# ClarityMezzanine_V2.net
KiCad netlist of a schematic drawn in Altium Designer
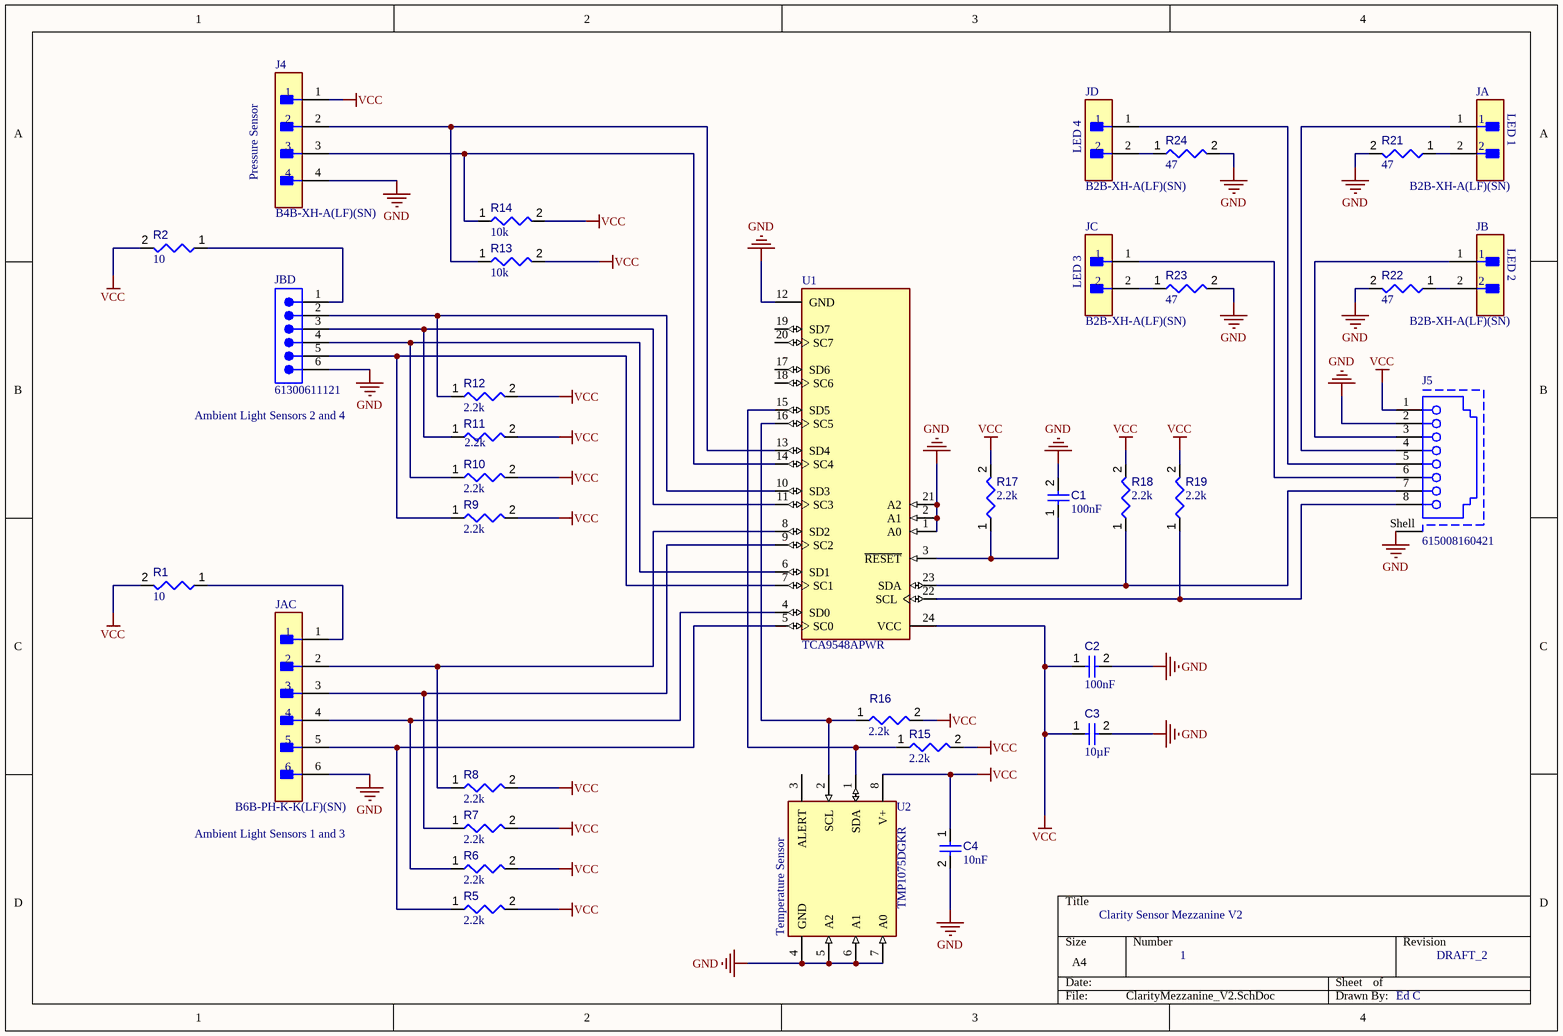
[diagram p0: ClarityMezzanine_V2.SchDoc]

(export (version "E")
  (design (tool "Eeschema 10.0.6"))
  (components
    (comp (ref "C1")
      (value "100nF")
      (footprint "CAPC2013X95X50LL10T25")
      (description "Chip Capacitor, 100 nF, +/- 10%, 50 V, 0805 (2012 Metric)")
      (fields (field (name "TOLERANCE") "10%") (field (name "Comment") "Capacitor 100 nF +/-10% 50 V 0805"))
      (libsource (lib "University of Auckland") (part "CAP-NP-2"))
    )
    (comp (ref "C2")
      (value "100nF")
      (footprint "CAPC2013X95X50LL10T25")
      (description "Chip Capacitor, 100 nF, +/- 10%, 50 V, 0805 (2012 Metric)")
      (fields (field (name "TOLERANCE") "10%") (field (name "Comment") "Capacitor 100 nF +/-10% 50 V 0805"))
      (libsource (lib "University of Auckland") (part "CAP-NP-2"))
    )
    (comp (ref "C3")
      (value "10µF")
      (footprint "CAPC0805(2012)145_L")
      (description "Chip Capacitor, 10µF +/-20%, 25V, 0805, Thickness 1.45 mm")
      (fields (field (name "TOLERANCE") "10%") (field (name "Comment") "Capacitor 10µF +/-20% 25V 0805"))
      (libsource (lib "University of Auckland") (part "CAP-NP-2"))
    )
    (comp (ref "C4")
      (value "10nF")
      (footprint "FP-C0805C-DN-IPC_A")
      (fields (field (name "Comment") "C0805C103K2RACTU"))
      (libsource (lib "University of Auckland") (part "CAP-NP-2"))
    )
    (comp (ref "J4")
      (value "B4B-XH-A(LF)(SN)")
      (footprint "FP-B4B-XH-A_LF_SN-MFG")
      (description "Header for PCB; pitch 2.50mm; 4-contacts; THT male; top entry; 250V/3A")
      (libsource (lib "University of Auckland") (part "299a8cea1bdcbc3624fe62c390fa72c"))
    )
    (comp (ref "J5")
      (value "615008160421")
      (footprint "615008160421")
      (description "Rj45 Connector, Jack, 8P8C, 1Port Rohs Compliant: Yes")
      (libsource (lib "University of Auckland") (part "8P8C - 1 Port - Shielded"))
    )
    (comp (ref "JA")
      (value "B2B-XH-A(LF)(SN)")
      (footprint "FP-B2B-XH-A_LF_SN-MFG")
      (description "CONNECTOR HEADER, XH SERIES, 2 POSITION, 2.50MM, Press-Fit Solder, Detent Lock, Natural")
      (libsource (lib "") (part "3bc925449376181038e59eaffc5286c_1"))
    )
    (comp (ref "JAC")
      (value "B6B-PH-K-K(LF)(SN)")
      (footprint "FP-B6B-PH-K-K_LF_SN-MFG")
      (description "PH Series 6 Position 2 mm Pitch Through Hole Top Entry Shrouded Header")
      (libsource (lib "University of Auckland") (part "f2cb566baf1c37ab5a3b8e90bbeafd6"))
    )
    (comp (ref "JB")
      (value "B2B-XH-A(LF)(SN)")
      (footprint "FP-B2B-XH-A_LF_SN-MFG")
      (description "CONNECTOR HEADER, XH SERIES, 2 POSITION, 2.50MM, Press-Fit Solder, Detent Lock, Natural")
      (libsource (lib "") (part "3bc925449376181038e59eaffc5286c_1"))
    )
    (comp (ref "JBD")
      (value "61300611121")
      (footprint "61300611121")
      (libsource (lib "University of Auckland") (part "Header_Male_1R_06P"))
    )
    (comp (ref "JC")
      (value "B2B-XH-A(LF)(SN)")
      (footprint "FP-B2B-XH-A_LF_SN-MFG")
      (description "CONNECTOR HEADER, XH SERIES, 2 POSITION, 2.50MM, Press-Fit Solder, Detent Lock, Natural")
      (libsource (lib "University of Auckland") (part "3bc925449376181038e59eaffc5286c"))
    )
    (comp (ref "JD")
      (value "B2B-XH-A(LF)(SN)")
      (footprint "FP-B2B-XH-A_LF_SN-MFG")
      (description "CONNECTOR HEADER, XH SERIES, 2 POSITION, 2.50MM, Press-Fit Solder, Detent Lock, Natural")
      (libsource (lib "University of Auckland") (part "3bc925449376181038e59eaffc5286c"))
    )
    (comp (ref "R1")
      (value "10")
      (footprint "RESC2013X60X35ML10T20")
      (fields
        (field (name "TOLERANCE") "1%")
        (field (name "POWER") "125mW")
        (field (name "Comment") "RC0805FR-0710RL")
      )
      (libsource (lib "University of Auckland") (part "RES-2"))
    )
    (comp (ref "R2")
      (value "10")
      (footprint "RESC2013X60X35ML10T20")
      (fields
        (field (name "TOLERANCE") "1%")
        (field (name "POWER") "125mW")
        (field (name "Comment") "RC0805FR-0710RL")
      )
      (libsource (lib "University of Auckland") (part "RES-2"))
    )
    (comp (ref "R5")
      (value "2.2k")
      (footprint "FP-CRCW0805-e3-IPC_A")
      (fields
        (field (name "POWER") "125mW")
        (field (name "TOLERANCE") "1%")
        (field (name "Comment") "CRCW08052K20FKEA")
      )
      (libsource (lib "University of Auckland") (part "RES-2"))
    )
    (comp (ref "R6")
      (value "2.2k")
      (footprint "FP-CRCW0805-e3-IPC_A")
      (fields
        (field (name "POWER") "125mW")
        (field (name "TOLERANCE") "1%")
        (field (name "Comment") "CRCW08052K20FKEA")
      )
      (libsource (lib "University of Auckland") (part "RES-2"))
    )
    (comp (ref "R7")
      (value "2.2k")
      (footprint "FP-CRCW0805-e3-IPC_A")
      (fields
        (field (name "POWER") "125mW")
        (field (name "TOLERANCE") "1%")
        (field (name "Comment") "CRCW08052K20FKEA")
      )
      (libsource (lib "University of Auckland") (part "RES-2"))
    )
    (comp (ref "R8")
      (value "2.2k")
      (footprint "FP-CRCW0805-e3-IPC_A")
      (fields
        (field (name "POWER") "125mW")
        (field (name "TOLERANCE") "1%")
        (field (name "Comment") "CRCW08052K20FKEA")
      )
      (libsource (lib "University of Auckland") (part "RES-2"))
    )
    (comp (ref "R9")
      (value "2.2k")
      (footprint "FP-CRCW0805-e3-IPC_A")
      (fields
        (field (name "POWER") "125mW")
        (field (name "TOLERANCE") "1%")
        (field (name "Comment") "CRCW08052K20FKEA")
      )
      (libsource (lib "University of Auckland") (part "RES-2"))
    )
    (comp (ref "R10")
      (value "2.2k")
      (footprint "FP-CRCW0805-e3-IPC_A")
      (fields
        (field (name "POWER") "125mW")
        (field (name "TOLERANCE") "1%")
        (field (name "Comment") "CRCW08052K20FKEA")
      )
      (libsource (lib "University of Auckland") (part "RES-2"))
    )
    (comp (ref "R11")
      (value "2.2k")
      (footprint "FP-CRCW0805-e3-IPC_A")
      (fields
        (field (name "POWER") "125mW")
        (field (name "TOLERANCE") "1%")
        (field (name "Comment") "CRCW08052K20FKEA")
      )
      (libsource (lib "University of Auckland") (part "RES-2"))
    )
    (comp (ref "R12")
      (value "2.2k")
      (footprint "FP-CRCW0805-e3-IPC_A")
      (fields
        (field (name "POWER") "125mW")
        (field (name "TOLERANCE") "1%")
        (field (name "Comment") "CRCW08052K20FKEA")
      )
      (libsource (lib "University of Auckland") (part "RES-2"))
    )
    (comp (ref "R13")
      (value "10k")
      (footprint "RESC2013X50X35ML15T15")
      (description "Chip Resistor, 10 KOhm, +/- 1%, 125 mW, -55 to 155 degC, 0805 (2012 Metric)")
      (fields (field (name "TOLERANCE") "1%") (field (name "POWER") "125mW"))
      (libsource (lib "University of Auckland") (part "RES-2"))
    )
    (comp (ref "R14")
      (value "10k")
      (footprint "RESC2013X50X35ML15T15")
      (description "Chip Resistor, 10 KOhm, +/- 1%, 125 mW, -55 to 155 degC, 0805 (2012 Metric)")
      (fields (field (name "TOLERANCE") "1%") (field (name "POWER") "125mW"))
      (libsource (lib "University of Auckland") (part "RES-2"))
    )
    (comp (ref "R15")
      (value "2.2k")
      (footprint "FP-CRCW0805-e3-IPC_A")
      (fields
        (field (name "POWER") "125mW")
        (field (name "TOLERANCE") "1%")
        (field (name "Comment") "CRCW08052K20FKEA")
      )
      (libsource (lib "University of Auckland") (part "RES-2"))
    )
    (comp (ref "R16")
      (value "2.2k")
      (footprint "FP-CRCW0805-e3-IPC_A")
      (fields
        (field (name "POWER") "125mW")
        (field (name "TOLERANCE") "1%")
        (field (name "Comment") "CRCW08052K20FKEA")
      )
      (libsource (lib "University of Auckland") (part "RES-2"))
    )
    (comp (ref "R17")
      (value "2.2k")
      (footprint "FP-CRCW0805-e3-IPC_A")
      (fields
        (field (name "POWER") "125mW")
        (field (name "TOLERANCE") "1%")
        (field (name "Comment") "CRCW08052K20FKEA")
      )
      (libsource (lib "University of Auckland") (part "RES-2"))
    )
    (comp (ref "R18")
      (value "2.2k")
      (footprint "FP-CRCW0805-e3-IPC_A")
      (fields
        (field (name "POWER") "125mW")
        (field (name "TOLERANCE") "1%")
        (field (name "Comment") "CRCW08052K20FKEA")
      )
      (libsource (lib "University of Auckland") (part "RES-2"))
    )
    (comp (ref "R19")
      (value "2.2k")
      (footprint "FP-CRCW0805-e3-IPC_A")
      (fields
        (field (name "POWER") "125mW")
        (field (name "TOLERANCE") "1%")
        (field (name "Comment") "CRCW08052K20FKEA")
      )
      (libsource (lib "University of Auckland") (part "RES-2"))
    )
    (comp (ref "R21")
      (value "47")
      (footprint "FP-ERJ6EN-IPC_B")
      (fields
        (field (name "TOLERANCE") "1%")
        (field (name "POWER") "125mW")
        (field (name "Comment") "ERJ-6ENF47R0V")
      )
      (libsource (lib "University of Auckland") (part "RES-2"))
    )
    (comp (ref "R22")
      (value "47")
      (footprint "FP-ERJ6EN-IPC_B")
      (fields
        (field (name "TOLERANCE") "1%")
        (field (name "POWER") "125mW")
        (field (name "Comment") "ERJ-6ENF47R0V")
      )
      (libsource (lib "University of Auckland") (part "RES-2"))
    )
    (comp (ref "R23")
      (value "47")
      (footprint "FP-ERJ6EN-IPC_B")
      (fields
        (field (name "TOLERANCE") "1%")
        (field (name "POWER") "125mW")
        (field (name "Comment") "ERJ-6ENF47R0V")
      )
      (libsource (lib "University of Auckland") (part "RES-2"))
    )
    (comp (ref "R24")
      (value "47")
      (footprint "FP-ERJ6EN-IPC_B")
      (fields
        (field (name "TOLERANCE") "1%")
        (field (name "POWER") "125mW")
        (field (name "Comment") "ERJ-6ENF47R0V")
      )
      (libsource (lib "University of Auckland") (part "RES-2"))
    )
    (comp (ref "U1")
      (value "TCA9548APWR")
      (footprint "FP-PW0024A-MFG")
      (description "Multiplexer, 9548 Series, 1-Func, 1 Line Input, 8 Line Output, True Output, PDSO24")
      (libsource (lib "University of Auckland") (part "aab65143522579f0e88a32f493a4230"))
    )
    (comp (ref "U2")
      (value "TMP1075DGKR")
      (footprint "FP-DGK0008A-IPC_A")
      (description "Serial Switch/Digital Sensor, 12 Bit(s), 2Cel, Square, Surface Mount")
      (libsource (lib "University of Auckland") (part "bfddf12e45925052cd02cc7c071e68b"))
    )
  )
  (nets
    (net (code "1") (name "GND") (class "Default")
      (node (ref "C1") (pin "2") (pinfunction "2_2") (pintype "passive"))
      (node (ref "C2") (pin "2") (pinfunction "2_2") (pintype "passive"))
      (node (ref "C3") (pin "2") (pinfunction "2_2") (pintype "passive"))
      (node (ref "C4") (pin "2") (pinfunction "2_2") (pintype "passive"))
      (node (ref "J4") (pin "4") (pinfunction "4_4") (pintype "passive"))
      (node (ref "J5") (pin "2") (pinfunction "2_2") (pintype "passive"))
      (node (ref "J5") (pin "Shell") (pinfunction "Shell_Shell") (pintype "passive"))
      (node (ref "JAC") (pin "6") (pinfunction "6_6") (pintype "passive"))
      (node (ref "JBD") (pin "6") (pinfunction "6_6") (pintype "passive"))
      (node (ref "R21") (pin "2") (pinfunction "2_2") (pintype "passive"))
      (node (ref "R22") (pin "2") (pinfunction "2_2") (pintype "passive"))
      (node (ref "R23") (pin "2") (pinfunction "2_2") (pintype "passive"))
      (node (ref "R24") (pin "2") (pinfunction "2_2") (pintype "passive"))
      (node (ref "U1") (pin "1") (pinfunction "A0_1") (pintype "input"))
      (node (ref "U1") (pin "12") (pinfunction "GND_12") (pintype "power_in"))
      (node (ref "U1") (pin "2") (pinfunction "A1_2") (pintype "input"))
      (node (ref "U1") (pin "21") (pinfunction "A2_21") (pintype "input"))
      (node (ref "U2") (pin "4") (pinfunction "GND_4") (pintype "power_in"))
      (node (ref "U2") (pin "5") (pinfunction "A2_5") (pintype "input"))
      (node (ref "U2") (pin "6") (pinfunction "A1_6") (pintype "input"))
      (node (ref "U2") (pin "7") (pinfunction "A0_7") (pintype "input"))
    )
    (net (code "2") (name "Net-(J5-Pad3)") (class "Default")
      (node (ref "J5") (pin "3") (pinfunction "3_3") (pintype "passive"))
      (node (ref "JB") (pin "1") (pinfunction "1_1") (pintype "passive"))
    )
    (net (code "3") (name "Net-(J5-Pad4)") (class "Default")
      (node (ref "J5") (pin "4") (pinfunction "4_4") (pintype "passive"))
      (node (ref "JA") (pin "1") (pinfunction "1_1") (pintype "passive"))
    )
    (net (code "4") (name "Net-(J5-Pad5)") (class "Default")
      (node (ref "J5") (pin "5") (pinfunction "5_5") (pintype "passive"))
      (node (ref "JD") (pin "1") (pinfunction "1_1") (pintype "passive"))
    )
    (net (code "5") (name "Net-(J5-Pad6)") (class "Default")
      (node (ref "J5") (pin "6") (pinfunction "6_6") (pintype "passive"))
      (node (ref "JC") (pin "1") (pinfunction "1_1") (pintype "passive"))
    )
    (net (code "6") (name "Net-(JA-Pad2)") (class "Default")
      (node (ref "JA") (pin "2") (pinfunction "2_2") (pintype "passive"))
      (node (ref "R21") (pin "1") (pinfunction "1_1") (pintype "passive"))
    )
    (net (code "7") (name "Net-(JAC-Pad1)") (class "Default")
      (node (ref "JAC") (pin "1") (pinfunction "1_1") (pintype "passive"))
      (node (ref "R1") (pin "1") (pinfunction "1_1") (pintype "passive"))
    )
    (net (code "8") (name "Net-(JB-Pad2)") (class "Default")
      (node (ref "JB") (pin "2") (pinfunction "2_2") (pintype "passive"))
      (node (ref "R22") (pin "1") (pinfunction "1_1") (pintype "passive"))
    )
    (net (code "9") (name "Net-(JBD-Pad1)") (class "Default")
      (node (ref "JBD") (pin "1") (pinfunction "1_1") (pintype "passive"))
      (node (ref "R2") (pin "1") (pinfunction "1_1") (pintype "passive"))
    )
    (net (code "10") (name "Net-(JC-Pad2)") (class "Default")
      (node (ref "JC") (pin "2") (pinfunction "2_2") (pintype "passive"))
      (node (ref "R23") (pin "1") (pinfunction "1_1") (pintype "passive"))
    )
    (net (code "11") (name "Net-(JD-Pad2)") (class "Default")
      (node (ref "JD") (pin "2") (pinfunction "2_2") (pintype "passive"))
      (node (ref "R24") (pin "1") (pinfunction "1_1") (pintype "passive"))
    )
    (net (code "12") (name "Net-(U1-SC0)") (class "Default")
      (node (ref "JAC") (pin "5") (pinfunction "5_5") (pintype "passive"))
      (node (ref "R5") (pin "1") (pinfunction "1_1") (pintype "passive"))
      (node (ref "U1") (pin "5") (pinfunction "SC0_5") (pintype "bidirectional"))
    )
    (net (code "13") (name "Net-(U1-SC1)") (class "Default")
      (node (ref "JBD") (pin "5") (pinfunction "5_5") (pintype "passive"))
      (node (ref "R9") (pin "1") (pinfunction "1_1") (pintype "passive"))
      (node (ref "U1") (pin "7") (pinfunction "SC1_7") (pintype "bidirectional"))
    )
    (net (code "14") (name "Net-(U1-SC2)") (class "Default")
      (node (ref "JAC") (pin "3") (pinfunction "3_3") (pintype "passive"))
      (node (ref "R7") (pin "1") (pinfunction "1_1") (pintype "passive"))
      (node (ref "U1") (pin "9") (pinfunction "SC2_9") (pintype "bidirectional"))
    )
    (net (code "15") (name "Net-(U1-SC3)") (class "Default")
      (node (ref "JBD") (pin "3") (pinfunction "3_3") (pintype "passive"))
      (node (ref "R11") (pin "1") (pinfunction "1_1") (pintype "passive"))
      (node (ref "U1") (pin "11") (pinfunction "SC3_11") (pintype "bidirectional"))
    )
    (net (code "16") (name "Net-(U1-SC4)") (class "Default")
      (node (ref "J4") (pin "3") (pinfunction "3_3") (pintype "passive"))
      (node (ref "R14") (pin "1") (pinfunction "1_1") (pintype "passive"))
      (node (ref "U1") (pin "14") (pinfunction "SC4_14") (pintype "bidirectional"))
    )
    (net (code "17") (name "Net-(U1-SC5)") (class "Default")
      (node (ref "R16") (pin "1") (pinfunction "1_1") (pintype "passive"))
      (node (ref "U1") (pin "16") (pinfunction "SC5_16") (pintype "bidirectional"))
      (node (ref "U2") (pin "2") (pinfunction "SCL_2") (pintype "input"))
    )
    (net (code "18") (name "Net-(U1-SCL)") (class "Default")
      (node (ref "J5") (pin "8") (pinfunction "8_8") (pintype "passive"))
      (node (ref "R19") (pin "1") (pinfunction "1_1") (pintype "passive"))
      (node (ref "U1") (pin "22") (pinfunction "SCL_22") (pintype "bidirectional"))
    )
    (net (code "19") (name "Net-(U1-SD0)") (class "Default")
      (node (ref "JAC") (pin "4") (pinfunction "4_4") (pintype "passive"))
      (node (ref "R6") (pin "1") (pinfunction "1_1") (pintype "passive"))
      (node (ref "U1") (pin "4") (pinfunction "SD0_4") (pintype "bidirectional"))
    )
    (net (code "20") (name "Net-(U1-SD1)") (class "Default")
      (node (ref "JBD") (pin "4") (pinfunction "4_4") (pintype "passive"))
      (node (ref "R10") (pin "1") (pinfunction "1_1") (pintype "passive"))
      (node (ref "U1") (pin "6") (pinfunction "SD1_6") (pintype "bidirectional"))
    )
    (net (code "21") (name "Net-(U1-SD2)") (class "Default")
      (node (ref "JAC") (pin "2") (pinfunction "2_2") (pintype "passive"))
      (node (ref "R8") (pin "1") (pinfunction "1_1") (pintype "passive"))
      (node (ref "U1") (pin "8") (pinfunction "SD2_8") (pintype "bidirectional"))
    )
    (net (code "22") (name "Net-(U1-SD3)") (class "Default")
      (node (ref "JBD") (pin "2") (pinfunction "2_2") (pintype "passive"))
      (node (ref "R12") (pin "1") (pinfunction "1_1") (pintype "passive"))
      (node (ref "U1") (pin "10") (pinfunction "SD3_10") (pintype "bidirectional"))
    )
    (net (code "23") (name "Net-(U1-SD4)") (class "Default")
      (node (ref "J4") (pin "2") (pinfunction "2_2") (pintype "passive"))
      (node (ref "R13") (pin "1") (pinfunction "1_1") (pintype "passive"))
      (node (ref "U1") (pin "13") (pinfunction "SD4_13") (pintype "bidirectional"))
    )
    (net (code "24") (name "Net-(U1-SD5)") (class "Default")
      (node (ref "R15") (pin "1") (pinfunction "1_1") (pintype "passive"))
      (node (ref "U1") (pin "15") (pinfunction "SD5_15") (pintype "bidirectional"))
      (node (ref "U2") (pin "1") (pinfunction "SDA_1") (pintype "bidirectional"))
    )
    (net (code "25") (name "Net-(U1-SDA)") (class "Default")
      (node (ref "J5") (pin "7") (pinfunction "7_7") (pintype "passive"))
      (node (ref "R18") (pin "1") (pinfunction "1_1") (pintype "passive"))
      (node (ref "U1") (pin "23") (pinfunction "SDA_23") (pintype "bidirectional"))
    )
    (net (code "26") (name "Net-(U1-~{RESET})") (class "Default")
      (node (ref "C1") (pin "1") (pinfunction "1_1") (pintype "passive"))
      (node (ref "R17") (pin "1") (pinfunction "1_1") (pintype "passive"))
      (node (ref "U1") (pin "3") (pinfunction "~{RESET}_3") (pintype "input"))
    )
    (net (code "27") (name "VCC") (class "Default")
      (node (ref "C2") (pin "1") (pinfunction "1_1") (pintype "passive"))
      (node (ref "C3") (pin "1") (pinfunction "1_1") (pintype "passive"))
      (node (ref "C4") (pin "1") (pinfunction "1_1") (pintype "passive"))
      (node (ref "J4") (pin "1") (pinfunction "1_1") (pintype "passive"))
      (node (ref "J5") (pin "1") (pinfunction "1_1") (pintype "passive"))
      (node (ref "R1") (pin "2") (pinfunction "2_2") (pintype "passive"))
      (node (ref "R10") (pin "2") (pinfunction "2_2") (pintype "passive"))
      (node (ref "R11") (pin "2") (pinfunction "2_2") (pintype "passive"))
      (node (ref "R12") (pin "2") (pinfunction "2_2") (pintype "passive"))
      (node (ref "R13") (pin "2") (pinfunction "2_2") (pintype "passive"))
      (node (ref "R14") (pin "2") (pinfunction "2_2") (pintype "passive"))
      (node (ref "R15") (pin "2") (pinfunction "2_2") (pintype "passive"))
      (node (ref "R16") (pin "2") (pinfunction "2_2") (pintype "passive"))
      (node (ref "R17") (pin "2") (pinfunction "2_2") (pintype "passive"))
      (node (ref "R18") (pin "2") (pinfunction "2_2") (pintype "passive"))
      (node (ref "R19") (pin "2") (pinfunction "2_2") (pintype "passive"))
      (node (ref "R2") (pin "2") (pinfunction "2_2") (pintype "passive"))
      (node (ref "R5") (pin "2") (pinfunction "2_2") (pintype "passive"))
      (node (ref "R6") (pin "2") (pinfunction "2_2") (pintype "passive"))
      (node (ref "R7") (pin "2") (pinfunction "2_2") (pintype "passive"))
      (node (ref "R8") (pin "2") (pinfunction "2_2") (pintype "passive"))
      (node (ref "R9") (pin "2") (pinfunction "2_2") (pintype "passive"))
      (node (ref "U1") (pin "24") (pinfunction "VCC_24") (pintype "power_in"))
      (node (ref "U2") (pin "8") (pinfunction "V+_8") (pintype "power_in"))
    )
    (net (code "28") (name "unconnected-(U1-SC6-Pad18)") (class "Default")
      (node (ref "U1") (pin "18") (pinfunction "SC6_18") (pintype "bidirectional"))
    )
    (net (code "29") (name "unconnected-(U1-SC7-Pad20)") (class "Default")
      (node (ref "U1") (pin "20") (pinfunction "SC7_20") (pintype "bidirectional"))
    )
    (net (code "30") (name "unconnected-(U1-SD6-Pad17)") (class "Default")
      (node (ref "U1") (pin "17") (pinfunction "SD6_17") (pintype "bidirectional"))
    )
    (net (code "31") (name "unconnected-(U1-SD7-Pad19)") (class "Default")
      (node (ref "U1") (pin "19") (pinfunction "SD7_19") (pintype "bidirectional"))
    )
    (net (code "32") (name "unconnected-(U2-ALERT-Pad3)") (class "Default")
      (node (ref "U2") (pin "3") (pinfunction "ALERT_3") (pintype "open_collector"))
    )
  )
)
